# Esp_schm.net
KiCad netlist of a schematic drawn in Altium Designer
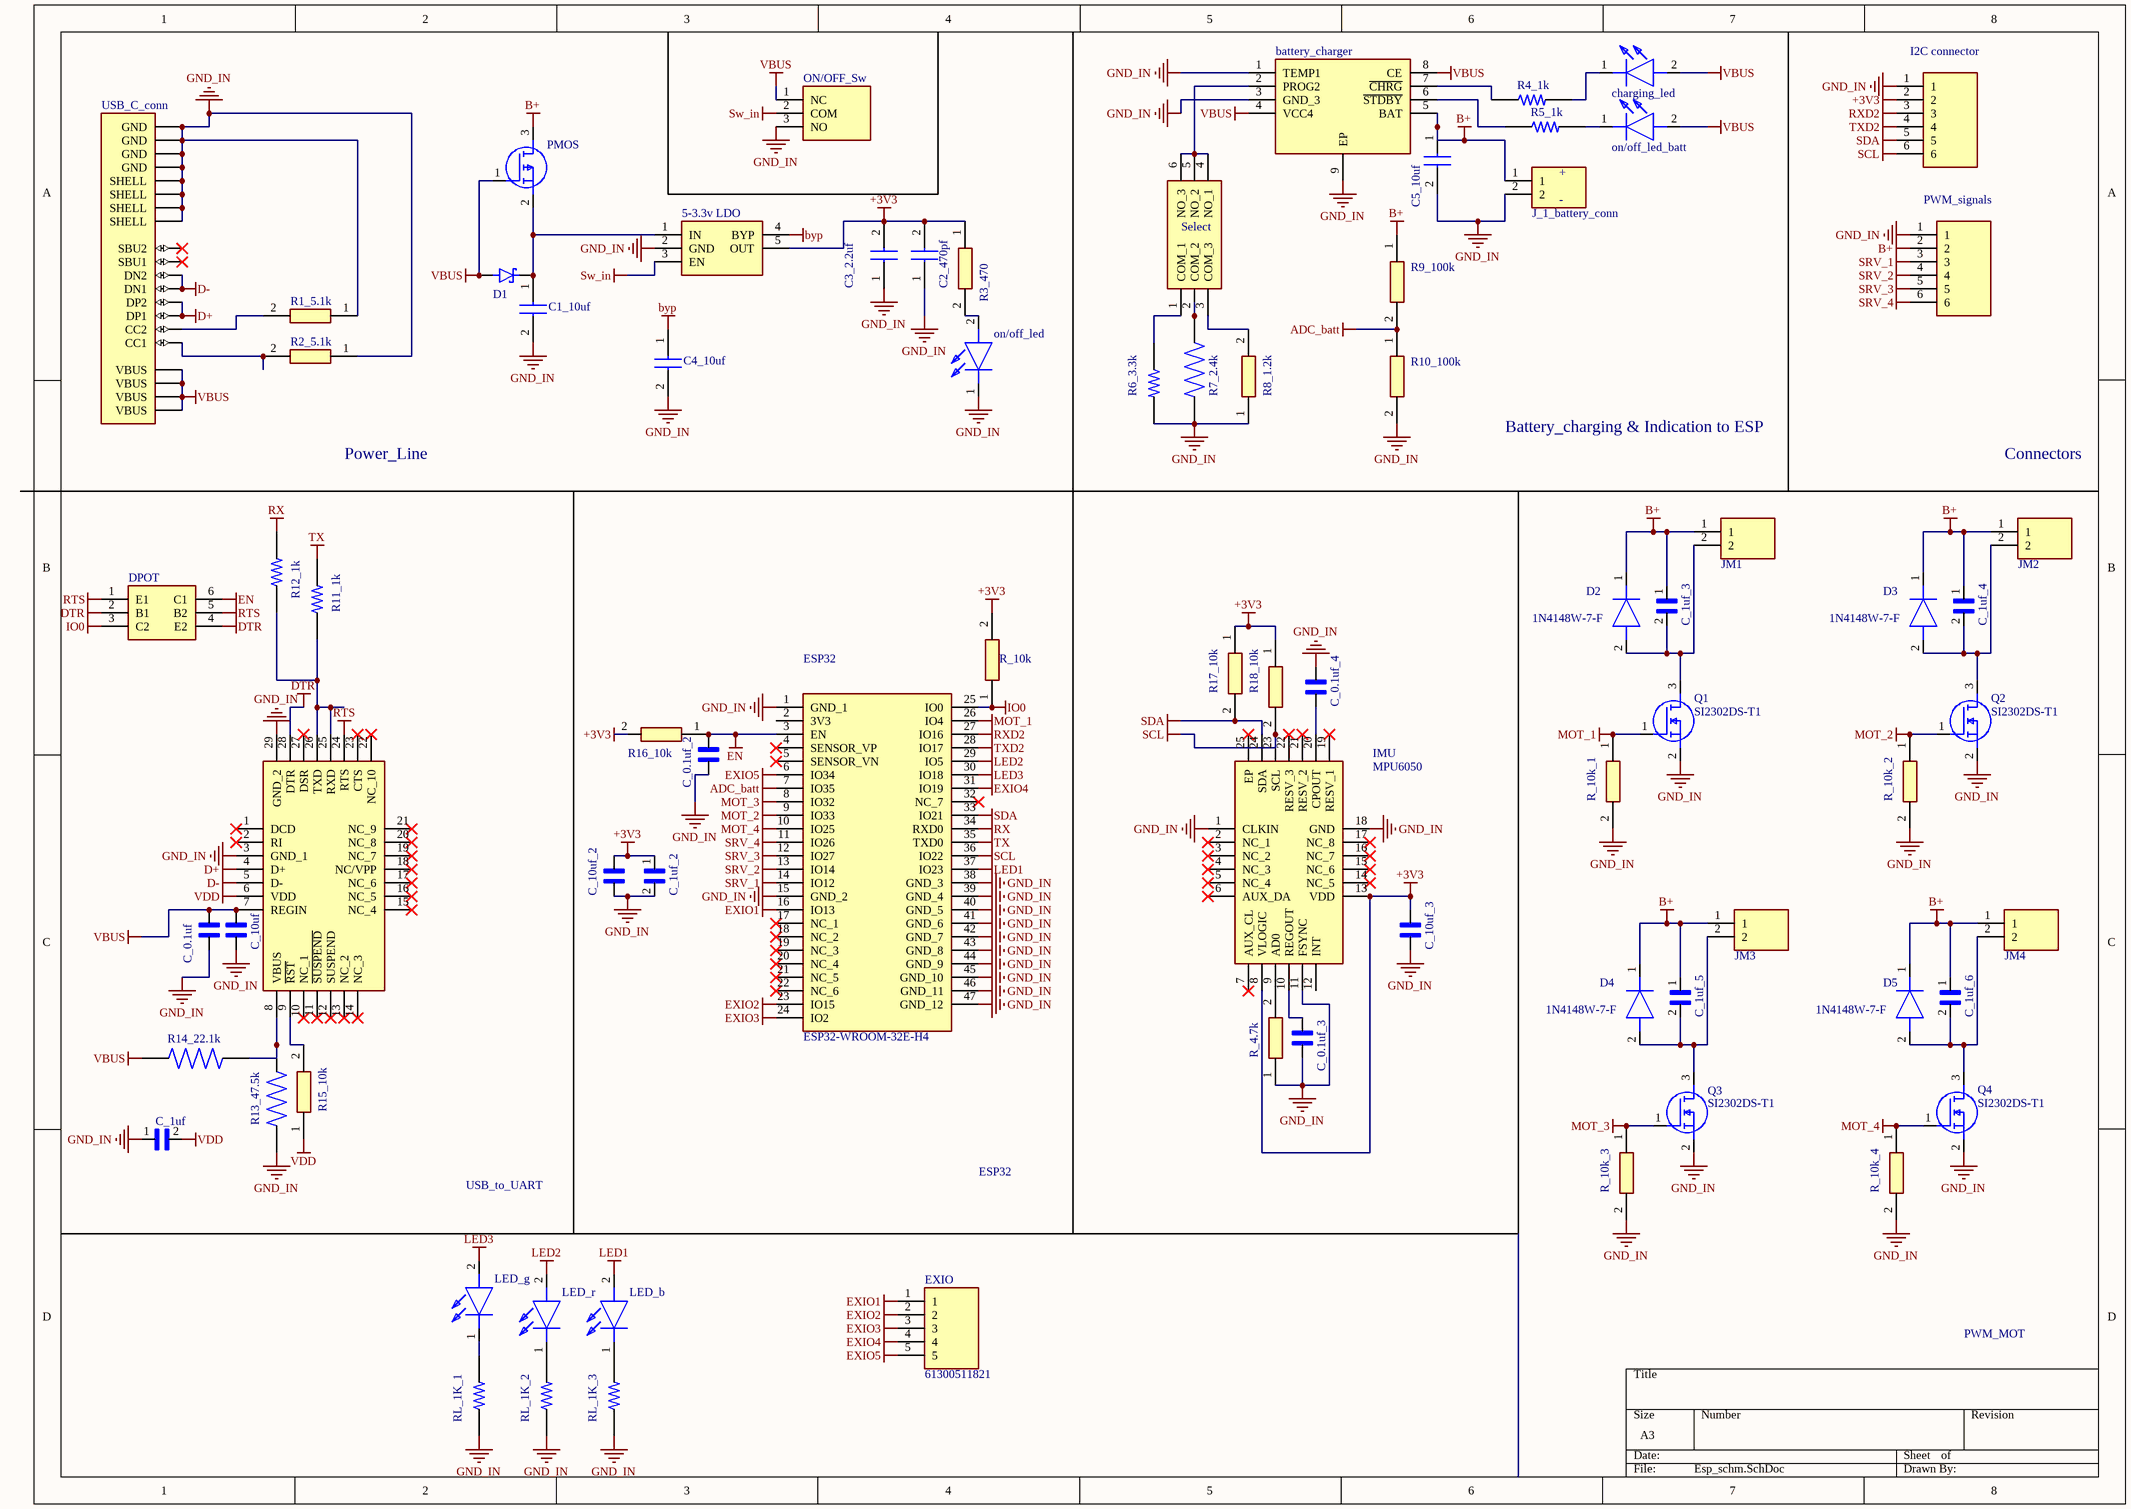
[diagram p0: Esp_schm.SchDoc]

(export (version "E")
  (design (tool "Eeschema 10.0.6"))
  (components
    (comp (ref "5-3.3v LDO")
      (value "MIC5219-3.3YM5-TR")
      (footprint "PcbLib1:SOT95P280X145-5N")
      (description "Integrated Circuit")
      (fields (field (name "MOUSER PART NUMBER") "998-MIC5219-3.3YM5TR"))
      (libsource (lib "*") (part "MIC5219-3.3YM5-TR"))
    )
    (comp (ref "battery_charger")
      (value "TP4056")
      (footprint "PcbLib1:SOIC127P600X175-9N")
      (description "Connector")
      (libsource (lib "*") (part "TP4056"))
    )
    (comp (ref "C1_10uf")
      (value "CGA3EDX7T1A106M080AU")
      (footprint "PcbLib1:CAPC1608X90N")
      (description "Capacitor")
      (fields (field (name "MOUSER PART NUMBER") "810-CGA3EDX7T1A106M0"))
      (libsource (lib "*") (part "CGA3EDX7T1A106M080AU"))
    )
    (comp (ref "C2_470pf")
      (value "02015C471KAT2A")
      (footprint "PcbLib1:CAPC0603X33N")
      (description "Capacitor")
      (fields (field (name "MOUSER PART NUMBER") "581-02015C471KAT2A"))
      (libsource (lib "*") (part "02015C471KAT2A"))
    )
    (comp (ref "C3_2.2uf")
      (value "CL03A225MO5C65C")
      (footprint "PcbLib1:CAPC0603X35N")
      (description "Capacitor")
      (fields (field (name "MOUSER PART NUMBER") "187-CL03A225MO5C65C"))
      (libsource (lib "*") (part "CL03A225MO5C65C"))
    )
    (comp (ref "C4_10uf")
      (value "CGA3EDX7T1A106M080AU")
      (footprint "PcbLib1:CAPC1608X90N")
      (description "Capacitor")
      (fields (field (name "MOUSER PART NUMBER") "810-CGA3EDX7T1A106M0"))
      (libsource (lib "*") (part "CGA3EDX7T1A106M080AU"))
    )
    (comp (ref "C5_10uf")
      (value "CGA3EDX7T1A106M080AU")
      (footprint "PcbLib1:CAPC1608X90N")
      (description "Capacitor")
      (fields (field (name "MOUSER PART NUMBER") "810-CGA3EDX7T1A106M0"))
      (libsource (lib "*") (part "CGA3EDX7T1A106M080AU"))
    )
    (comp (ref "charging_led")
      (value "SML-D12U1WT86")
      (footprint "PcbLib1:LEDC1608X65N")
      (description "LED")
      (fields (field (name "MOUSER PART NUMBER") "755-SML-D12U1WT86"))
      (libsource (lib "*") (part "SML-D12U1WT86"))
    )
    (comp (ref "C_0.1uf")
      (value "GCM188R71C104KA37J")
      (footprint "CAPC1608X90N")
      (description "SMD Capacitor X7R(EIA) with Capacitance: 0.10uF Tol. 10%. Rated Voltage: 16Vdc")
      (fields (field (name "MF") "Murata"))
      (libsource (lib "GCM188R71C104KA37J") (part "GCM188R71C104KA37J"))
    )
    (comp (ref "C_0.1uf_2")
      (value "GCM188R71C104KA37J")
      (footprint "CAPC1608X90N")
      (description "SMD Capacitor X7R(EIA) with Capacitance: 0.10uF Tol. 10%. Rated Voltage: 16Vdc")
      (fields (field (name "MF") "Murata"))
      (libsource (lib "GCM188R71C104KA37J") (part "GCM188R71C104KA37J"))
    )
    (comp (ref "C_0.1uf_3")
      (value "GCM188R71C104KA37J")
      (footprint "CAPC1608X90N")
      (description "SMD Capacitor X7R(EIA) with Capacitance: 0.10uF Tol. 10%. Rated Voltage: 16Vdc")
      (fields (field (name "MF") "Murata"))
      (libsource (lib "GCM188R71C104KA37J") (part "GCM188R71C104KA37J"))
    )
    (comp (ref "C_0.1uf_4")
      (value "GCM188R71C104KA37J")
      (footprint "CAPC1608X90N")
      (description "SMD Capacitor X7R(EIA) with Capacitance: 0.10uF Tol. 10%. Rated Voltage: 16Vdc")
      (fields (field (name "MF") "Murata"))
      (libsource (lib "GCM188R71C104KA37J") (part "GCM188R71C104KA37J"))
    )
    (comp (ref "C_1uf")
      (value "C1608X7R1C105K080AC")
      (footprint "CAPC1608X90N:CAPC1608X90N")
      (description "1ÂµF Â±10% 16V Ceramic Capacitor X7R 0603 (1608 Metric)")
      (fields (field (name "MF") "TDK"))
      (libsource (lib "Schlib1") (part "C1608X7R1C105K080AC"))
    )
    (comp (ref "C_1uf_2")
      (value "C1608X7R1C105K080AC")
      (footprint "CAPC1608X90N:CAPC1608X90N")
      (description "1ÂµF Â±10% 16V Ceramic Capacitor X7R 0603 (1608 Metric)")
      (fields (field (name "MF") "TDK"))
      (libsource (lib "") (part "C1608X7R1C105K080AC_1"))
    )
    (comp (ref "C_1uf_3")
      (value "C1608X7R1C105K080AC")
      (footprint "CAPC1608X90N:CAPC1608X90N")
      (description "1ÂµF Â±10% 16V Ceramic Capacitor X7R 0603 (1608 Metric)")
      (fields (field (name "MF") "TDK"))
      (libsource (lib "") (part "C1608X7R1C105K080AC_1"))
    )
    (comp (ref "C_1uf_4")
      (value "C1608X7R1C105K080AC")
      (footprint "CAPC1608X90N:CAPC1608X90N")
      (description "1ÂµF Â±10% 16V Ceramic Capacitor X7R 0603 (1608 Metric)")
      (fields (field (name "MF") "TDK"))
      (libsource (lib "") (part "C1608X7R1C105K080AC_1"))
    )
    (comp (ref "C_1uf_5")
      (value "C1608X7R1C105K080AC")
      (footprint "CAPC1608X90N:CAPC1608X90N")
      (description "1ÂµF Â±10% 16V Ceramic Capacitor X7R 0603 (1608 Metric)")
      (fields (field (name "MF") "TDK"))
      (libsource (lib "") (part "C1608X7R1C105K080AC_1"))
    )
    (comp (ref "C_1uf_6")
      (value "C1608X7R1C105K080AC")
      (footprint "CAPC1608X90N:CAPC1608X90N")
      (description "1ÂµF Â±10% 16V Ceramic Capacitor X7R 0603 (1608 Metric)")
      (fields (field (name "MF") "TDK"))
      (libsource (lib "") (part "C1608X7R1C105K080AC_1"))
    )
    (comp (ref "C_10uf")
      (value "GRT188R61C106KE13J_1")
      (footprint "CAPC1608X95N")
      (description "SMD capacitor X5R(EIA) with capacitance 10uF Tol.10%. Rated voltage 16Vdc 85C")
      (fields (field (name "MF") "Murata") (field (name "MP") "GRT188R61C106KE13J"))
      (libsource (lib "Schlib1") (part "GRT188R61C106KE13J_1"))
    )
    (comp (ref "C_10uf_2")
      (value "GRT188R61C106KE13J_1")
      (footprint "CAPC1608X95N")
      (description "SMD capacitor X5R(EIA) with capacitance 10uF Tol.10%. Rated voltage 16Vdc 85C")
      (fields (field (name "MF") "Murata") (field (name "MP") "GRT188R61C106KE13J"))
      (libsource (lib "Schlib1") (part "GRT188R61C106KE13J_1"))
    )
    (comp (ref "C_10uf_3")
      (value "GRT188R61C106KE13J_1")
      (footprint "CAPC1608X95N")
      (description "SMD capacitor X5R(EIA) with capacitance 10uF Tol.10%. Rated voltage 16Vdc 85C")
      (fields (field (name "MF") "Murata") (field (name "MP") "GRT188R61C106KE13J"))
      (libsource (lib "Schlib1") (part "GRT188R61C106KE13J_1"))
    )
    (comp (ref "D1")
      (value "SS34")
      (footprint "DIOM7959X265N")
      (description "Diode Schottky 40 V 3A Surface Mount SMC (DO-214AB)")
      (fields (field (name "MF") "onsemi"))
      (libsource (lib "Schlib1") (part "SS34"))
    )
    (comp (ref "D2")
      (value "1N4148W-7-F")
      (footprint "PcbLib1:1N4148W7F")
      (description "Diode")
      (libsource (lib "*") (part "1N4148W-7-F"))
    )
    (comp (ref "D3")
      (value "1N4148W-7-F")
      (footprint "PcbLib1:1N4148W7F")
      (description "Diode")
      (libsource (lib "*") (part "1N4148W-7-F"))
    )
    (comp (ref "D4")
      (value "1N4148W-7-F")
      (footprint "PcbLib1:1N4148W7F")
      (description "Diode")
      (libsource (lib "*") (part "1N4148W-7-F"))
    )
    (comp (ref "D5")
      (value "1N4148W-7-F")
      (footprint "PcbLib1:1N4148W7F")
      (description "Diode")
      (libsource (lib "*") (part "1N4148W-7-F"))
    )
    (comp (ref "DPOT")
      (value "DDC114TU-7-F")
      (footprint "PcbLib1:SOT65P210X110-6N")
      (description "Transistor BJT NPN")
      (fields (field (name "MOUSER PART NUMBER") "621-DDC114TU-F"))
      (libsource (lib "*") (part "DDC114TU-7-F"))
    )
    (comp (ref "ESP32")
      (value "ESP32-WROOM-32E-H4")
      (footprint "PcbLib1:ESP32WROOM32EH4")
      (description "Integrated Circuit")
      (fields (field (name "MOUSER PART NUMBER") "356-ESP32WRM320EH3PS"))
      (libsource (lib "*") (part "ESP32-WROOM-32E-H4"))
    )
    (comp (ref "EXIO")
      (value "61300511821")
      (footprint "PcbLib1:61300511821")
      (description "Connector")
      (fields (field (name "MOUSER PART NUMBER") "710-61300511821"))
      (libsource (lib "*") (part "61300511821"))
    )
    (comp (ref "I2C connector")
      (value "B6B-XH-A_LF__SN_")
      (footprint "PcbLib1:SHDR6W64P0X250_1X6_1740X575X700P")
      (description "Connector")
      (fields
        (field (name "MANUFACTURER_PART_NUMBER") "B6B-XH-A(LF)(SN)")
        (field (name "MOUSER PART NUMBER") "306-B6BXHALFSN")
      )
      (libsource (lib "*") (part "B6B-XH-A_LF__SN_"))
    )
    (comp (ref "IMU")
      (value "MPU6050")
      (footprint "PcbLib1:MPU6050")
      (description "Integrated Circuit")
      (libsource (lib "*") (part "MPU6050"))
    )
    (comp (ref "JM1")
      (value "B2B-XH-A_LF__SN_")
      (footprint "PcbLib1:SHDR2W64P0X250_1X2_740X575X700P")
      (description "Connector")
      (fields
        (field (name "MANUFACTURER_PART_NUMBER") "B2B-XH-A(LF)(SN)")
        (field (name "MOUSER PART NUMBER") "306-B2BXHALFSNP")
      )
      (libsource (lib "*") (part "B2B-XH-A_LF__SN_"))
    )
    (comp (ref "JM2")
      (value "B2B-XH-A_LF__SN_")
      (footprint "PcbLib1:SHDR2W64P0X250_1X2_740X575X700P")
      (description "Connector")
      (fields
        (field (name "MANUFACTURER_PART_NUMBER") "B2B-XH-A(LF)(SN)")
        (field (name "MOUSER PART NUMBER") "306-B2BXHALFSNP")
      )
      (libsource (lib "*") (part "B2B-XH-A_LF__SN_"))
    )
    (comp (ref "JM3")
      (value "B2B-XH-A_LF__SN_")
      (footprint "PcbLib1:SHDR2W64P0X250_1X2_740X575X700P")
      (description "Connector")
      (fields
        (field (name "MANUFACTURER_PART_NUMBER") "B2B-XH-A(LF)(SN)")
        (field (name "MOUSER PART NUMBER") "306-B2BXHALFSNP")
      )
      (libsource (lib "*") (part "B2B-XH-A_LF__SN_"))
    )
    (comp (ref "JM4")
      (value "B2B-XH-A_LF__SN_")
      (footprint "PcbLib1:SHDR2W64P0X250_1X2_740X575X700P")
      (description "Connector")
      (fields
        (field (name "MANUFACTURER_PART_NUMBER") "B2B-XH-A(LF)(SN)")
        (field (name "MOUSER PART NUMBER") "306-B2BXHALFSNP")
      )
      (libsource (lib "*") (part "B2B-XH-A_LF__SN_"))
    )
    (comp (ref "J_1_battery_conn")
      (value "B2B-XH-A_LF__SN_")
      (footprint "PcbLib1:SHDR2W64P0X250_1X2_740X575X700P")
      (description "Connector")
      (fields
        (field (name "MANUFACTURER_PART_NUMBER") "B2B-XH-A(LF)(SN)")
        (field (name "MOUSER PART NUMBER") "306-B2BXHALFSNP")
      )
      (libsource (lib "*") (part "B2B-XH-A_LF__SN_"))
    )
    (comp (ref "LED_b")
      (value "150060BS55040")
      (footprint "PcbLib1:LEDC1608X50N")
      (description "LED")
      (fields (field (name "MOUSER PART NUMBER") "710-150060BS55040"))
      (libsource (lib "*") (part "150060BS55040"))
    )
    (comp (ref "LED_g")
      (value "ASMT-RF45-AN002")
      (footprint "PcbLib1:LEDC1608X55N")
      (description "LED")
      (fields (field (name "MOUSER PART NUMBER") "630-ASMT-RF45-AN002"))
      (libsource (lib "*") (part "ASMT-RF45-AN002"))
    )
    (comp (ref "LED_r")
      (value "KR_DELPS1.22-VGVI-23-H3Q4")
      (footprint "PcbLib1:KRDELPS122VGVI23H3Q4")
      (description "LED")
      (fields
        (field (name "MANUFACTURER_PART_NUMBER") "KR DELPS1.22-VGVI-23-H3Q4")
        (field (name "MOUSER PART NUMBER") "720-KRDELPS122VGVI3H")
      )
      (libsource (lib "*") (part "KR_DELPS1.22-VGVI-23-H3Q4"))
    )
    (comp (ref "on/off_led")
      (value "LB_Q39G-L2OO-35-1")
      (footprint "PcbLib1:LEDC1608X40N")
      (description "LED")
      (fields
        (field (name "MANUFACTURER_PART_NUMBER") "LB Q39G-L2OO-35-1")
        (field (name "MOUSER PART NUMBER") "720-LBQ39GL2N2351")
      )
      (libsource (lib "*") (part "LB_Q39G-L2OO-35-1"))
    )
    (comp (ref "on/off_led_batt")
      (value "LB_Q39G-L2OO-35-1")
      (footprint "PcbLib1:LEDC1608X40N")
      (description "LED")
      (fields
        (field (name "MANUFACTURER_PART_NUMBER") "LB Q39G-L2OO-35-1")
        (field (name "MOUSER PART NUMBER") "720-LBQ39GL2N2351")
      )
      (libsource (lib "*") (part "LB_Q39G-L2OO-35-1"))
    )
    (comp (ref "ON/OFF_Sw")
      (value "SLW-883935-2A-D")
      (footprint "PcbLib1:SLW8839352AD")
      (description "Switch")
      (fields (field (name "MOUSER PART NUMBER") "179-SLW-883935-2A-D"))
      (libsource (lib "*") (part "SLW-883935-2A-D"))
    )
    (comp (ref "PMOS")
      (value "AO3401A")
      (footprint "SamacSys:SOT95P280X125-3N")
      (description "MOSFET (P-Channel)")
      (libsource (lib "*") (part "AO3401A"))
    )
    (comp (ref "PWM_signals")
      (value "B6B-XH-A_LF__SN_")
      (footprint "PcbLib1:SHDR6W64P0X250_1X6_1740X575X700P")
      (description "Connector")
      (fields
        (field (name "MANUFACTURER_PART_NUMBER") "B6B-XH-A(LF)(SN)")
        (field (name "MOUSER PART NUMBER") "306-B6BXHALFSN")
      )
      (libsource (lib "*") (part "B6B-XH-A_LF__SN_"))
    )
    (comp (ref "Q1")
      (value "SI2302DS-T1")
      (footprint "PcbLib1:SOT95P237X112-3N")
      (description "MOSFET (N-Channel)")
      (fields (field (name "MOUSER PART NUMBER") "781-SI2302DS"))
      (libsource (lib "*") (part "SI2302DS-T1"))
    )
    (comp (ref "Q2")
      (value "SI2302DS-T1")
      (footprint "PcbLib1:SOT95P237X112-3N")
      (description "MOSFET (N-Channel)")
      (fields (field (name "MOUSER PART NUMBER") "781-SI2302DS"))
      (libsource (lib "*") (part "SI2302DS-T1"))
    )
    (comp (ref "Q3")
      (value "SI2302DS-T1")
      (footprint "PcbLib1:SOT95P237X112-3N")
      (description "MOSFET (N-Channel)")
      (fields (field (name "MOUSER PART NUMBER") "781-SI2302DS"))
      (libsource (lib "*") (part "SI2302DS-T1"))
    )
    (comp (ref "Q4")
      (value "SI2302DS-T1")
      (footprint "PcbLib1:SOT95P237X112-3N")
      (description "MOSFET (N-Channel)")
      (fields (field (name "MOUSER PART NUMBER") "781-SI2302DS"))
      (libsource (lib "*") (part "SI2302DS-T1"))
    )
    (comp (ref "R1_5.1k")
      (value "ERA-3VEB5101V")
      (footprint "SamacSys:ERA3KV_(0603)")
      (description "Resistor")
      (fields (field (name "MOUSER PART NUMBER") "667-ERA-3VEB5101V"))
      (libsource (lib "Schlib1") (part "ERA-3VEB5101V"))
    )
    (comp (ref "R2_5.1k")
      (value "ERA-3VEB5101V")
      (footprint "SamacSys:ERA3KV_(0603)")
      (description "Resistor")
      (fields (field (name "MOUSER PART NUMBER") "667-ERA-3VEB5101V"))
      (libsource (lib "Schlib1") (part "ERA-3VEB5101V"))
    )
    (comp (ref "R3_470")
      (value "ERJ-1GJF4700C")
      (footprint "PcbLib1:ERJ1GJJ2R4C")
      (description "Resistor")
      (fields (field (name "MOUSER PART NUMBER") "667-ERJ-1GJF4700C"))
      (libsource (lib "*") (part "ERJ-1GJF4700C"))
    )
    (comp (ref "R4_1k")
      (value "RC0603FR-071KL")
      (footprint "RESC1607X60N")
      (description "1 kOhms Â±1% 0.1W, 1/10W Chip Resistor 0603 (1608 Metric) Moisture Resistant Thick Film")
      (fields (field (name "MF") "Yageo"))
      (libsource (lib "Schlib1") (part "RC0603FR-071KL"))
    )
    (comp (ref "R5_1k")
      (value "RC0603FR-071KL")
      (footprint "RESC1607X60N")
      (description "1 kOhms Â±1% 0.1W, 1/10W Chip Resistor 0603 (1608 Metric) Moisture Resistant Thick Film")
      (fields (field (name "MF") "Yageo"))
      (libsource (lib "Schlib1") (part "RC0603FR-071KL"))
    )
    (comp (ref "R6_3.3k")
      (value "RC0603FR-073K3L")
      (footprint "RESC1607X60N")
      (description "3.3 kOhms ±1% 0.1W, 1/10W Chip Resistor 0603 (1608 Metric) Moisture Resistant Thick Film")
      (fields (field (name "MF") "Yageo"))
      (libsource (lib "Schlib1") (part "RC0603FR-073K3L"))
    )
    (comp (ref "R7_2.4k")
      (value "RC0603FR-072K4L")
      (footprint "RESC1607X60N")
      (description "2.4 kOhms Â±1% 0.1W, 1/10W Chip Resistor 0603 (1608 Metric) Moisture Resistant Thick Film")
      (fields (field (name "MF") "Yageo"))
      (libsource (lib "Schlib1") (part "RC0603FR-072K4L"))
    )
    (comp (ref "R8_1.2k")
      (value "ERJ-3GEYJ122V")
      (footprint "PcbLib1:ERJ3EKF1000V")
      (description "Resistor")
      (fields (field (name "MOUSER PART NUMBER") "667-ERJ-3GEYJ122V"))
      (libsource (lib "*") (part "ERJ-3GEYJ122V"))
    )
    (comp (ref "R9_100k")
      (value "RC0805FR-7W100KL")
      (footprint "PcbLib1:RESC2012X60N")
      (description "Resistor")
      (fields (field (name "MOUSER PART NUMBER") "603-RC0805FR-7W100KL"))
      (libsource (lib "*") (part "RC0805FR-7W100KL"))
    )
    (comp (ref "R10_100k")
      (value "RC0805FR-7W100KL")
      (footprint "PcbLib1:RESC2012X60N")
      (description "Resistor")
      (fields (field (name "MOUSER PART NUMBER") "603-RC0805FR-7W100KL"))
      (libsource (lib "*") (part "RC0805FR-7W100KL"))
    )
    (comp (ref "R11_1k")
      (value "RC0603FR-071KL")
      (footprint "RESC1607X60N")
      (description "1 kOhms Â±1% 0.1W, 1/10W Chip Resistor 0603 (1608 Metric) Moisture Resistant Thick Film")
      (fields (field (name "MF") "Yageo"))
      (libsource (lib "Schlib1") (part "RC0603FR-071KL"))
    )
    (comp (ref "R12_1k")
      (value "RC0603FR-071KL")
      (footprint "RESC1607X60N")
      (description "1 kOhms Â±1% 0.1W, 1/10W Chip Resistor 0603 (1608 Metric) Moisture Resistant Thick Film")
      (fields (field (name "MF") "Yageo"))
      (libsource (lib "Schlib1") (part "RC0603FR-071KL"))
    )
    (comp (ref "R13_47.5k")
      (value "CRCW060347K5FKEA")
      (footprint "RESC1508X50N")
      (fields (field (name "MF") "Vishay"))
      (libsource (lib "Schlib1") (part "CRCW060347K5FKEA"))
    )
    (comp (ref "R14_22.1k")
      (value "CRCW060322K1FKEA")
      (footprint "RESC1508X50N")
      (fields (field (name "MF") "Vishay Dale"))
      (libsource (lib "CRCW060322K1FKEA") (part "CRCW060322K1FKEA"))
    )
    (comp (ref "R15_10k")
      (value "CRCW060310K0FKEA")
      (footprint "PcbLib1:RESC1608X50N")
      (description "Resistor")
      (fields (field (name "MOUSER PART NUMBER") "71-CRCW0603-10K-E3"))
      (libsource (lib "") (part "CRCW060310K0FKEA_2"))
    )
    (comp (ref "R16_10k")
      (value "CRCW060310K0FKEA")
      (footprint "PcbLib1:RESC1608X50N")
      (description "Resistor")
      (fields (field (name "MOUSER PART NUMBER") "71-CRCW0603-10K-E3"))
      (libsource (lib "*") (part "CRCW060310K0FKEA"))
    )
    (comp (ref "R17_10k")
      (value "CRCW060310K0FKEA")
      (footprint "PcbLib1:RESC1608X50N")
      (description "Resistor")
      (fields (field (name "MOUSER PART NUMBER") "71-CRCW0603-10K-E3"))
      (libsource (lib "") (part "CRCW060310K0FKEA_1"))
    )
    (comp (ref "R18_10k")
      (value "CRCW060310K0FKEA")
      (footprint "PcbLib1:RESC1608X50N")
      (description "Resistor")
      (fields (field (name "MOUSER PART NUMBER") "71-CRCW0603-10K-E3"))
      (libsource (lib "") (part "CRCW060310K0FKEA_1"))
    )
    (comp (ref "RL_1K_1")
      (value "RC0603FR-071KL")
      (footprint "RESC1607X60N")
      (description "1 kOhms Â±1% 0.1W, 1/10W Chip Resistor 0603 (1608 Metric) Moisture Resistant Thick Film")
      (fields (field (name "MF") "Yageo"))
      (libsource (lib "Schlib1") (part "RC0603FR-071KL"))
    )
    (comp (ref "RL_1K_2")
      (value "RC0603FR-071KL")
      (footprint "RESC1607X60N")
      (description "1 kOhms Â±1% 0.1W, 1/10W Chip Resistor 0603 (1608 Metric) Moisture Resistant Thick Film")
      (fields (field (name "MF") "Yageo"))
      (libsource (lib "Schlib1") (part "RC0603FR-071KL"))
    )
    (comp (ref "RL_1K_3")
      (value "RC0603FR-071KL")
      (footprint "RESC1607X60N")
      (description "1 kOhms Â±1% 0.1W, 1/10W Chip Resistor 0603 (1608 Metric) Moisture Resistant Thick Film")
      (fields (field (name "MF") "Yageo"))
      (libsource (lib "Schlib1") (part "RC0603FR-071KL"))
    )
    (comp (ref "R_4.7k")
      (value "GWCR0603-4K7FT5")
      (footprint "PcbLib1:RESC1608X55N")
      (description "Resistor")
      (fields (field (name "MOUSER PART NUMBER") "756-GWCR0603-4K7FT5"))
      (libsource (lib "*") (part "GWCR0603-4K7FT5"))
    )
    (comp (ref "R_10k")
      (value "CRCW060310K0FKEA")
      (footprint "PcbLib1:RESC1608X50N")
      (description "Resistor")
      (fields (field (name "MOUSER PART NUMBER") "71-CRCW0603-10K-E3"))
      (libsource (lib "") (part "CRCW060310K0FKEA_2"))
    )
    (comp (ref "R_10k_1")
      (value "CRCW060310K0FKEA")
      (footprint "PcbLib1:RESC1608X50N")
      (description "Resistor")
      (fields (field (name "MOUSER PART NUMBER") "71-CRCW0603-10K-E3"))
      (libsource (lib "") (part "CRCW060310K0FKEA_1"))
    )
    (comp (ref "R_10k_2")
      (value "CRCW060310K0FKEA")
      (footprint "PcbLib1:RESC1608X50N")
      (description "Resistor")
      (fields (field (name "MOUSER PART NUMBER") "71-CRCW0603-10K-E3"))
      (libsource (lib "") (part "CRCW060310K0FKEA_1"))
    )
    (comp (ref "R_10k_3")
      (value "CRCW060310K0FKEA")
      (footprint "PcbLib1:RESC1608X50N")
      (description "Resistor")
      (fields (field (name "MOUSER PART NUMBER") "71-CRCW0603-10K-E3"))
      (libsource (lib "") (part "CRCW060310K0FKEA_1"))
    )
    (comp (ref "R_10k_4")
      (value "CRCW060310K0FKEA")
      (footprint "PcbLib1:RESC1608X50N")
      (description "Resistor")
      (fields (field (name "MOUSER PART NUMBER") "71-CRCW0603-10K-E3"))
      (libsource (lib "") (part "CRCW060310K0FKEA_1"))
    )
    (comp (ref "Select")
      (value "DS01-254-S-03BE")
      (footprint "PcbLib1:DS01254S03BE")
      (description "Switch")
      (fields (field (name "MOUSER PART NUMBER") "490-DS01-254-S-03BE"))
      (libsource (lib "*") (part "DS01-254-S-03BE"))
    )
    (comp (ref "USB_C_conn")
      (value "USB4085-GF-A_REVB")
      (footprint "GCT_USB4085-GF-A_REVB")
      (fields (field (name "MF") "Global Connector Technology") (field (name "MP") "USB4085-GF-A"))
      (libsource (lib "Schlib1") (part "USB4085-GF-A_REVB"))
    )
    (comp (ref "USB_to_UART")
      (value "CP2102-GM")
      (footprint "PcbLib1:QFN50P500X500X100-29N-D")
      (description "Integrated Circuit")
      (fields (field (name "MOUSER PART NUMBER") "634-CP2102-GM"))
      (libsource (lib "*") (part "CP2102-GM"))
    )
  )
  (nets
    (net (code "1") (name "+3V3") (class "Default")
      (node (ref "5-3.3v LDO") (pin "5") (pinfunction "OUT_5") (pintype "passive"))
      (node (ref "C2_470pf") (pin "2") (pinfunction "2_2") (pintype "passive"))
      (node (ref "C3_2.2uf") (pin "2") (pinfunction "2_2") (pintype "passive"))
      (node (ref "C_10uf_2") (pin "2") (pinfunction "2_2") (pintype "passive"))
      (node (ref "C_10uf_3") (pin "2") (pinfunction "2_2") (pintype "passive"))
      (node (ref "C_1uf_2") (pin "1") (pinfunction "1_1") (pintype "passive"))
      (node (ref "I2C connector") (pin "2") (pinfunction "2_2") (pintype "passive"))
      (node (ref "IMU") (pin "13") (pinfunction "VDD_13") (pintype "passive"))
      (node (ref "IMU") (pin "8") (pinfunction "VLOGIC_8") (pintype "passive"))
      (node (ref "R16_10k") (pin "2") (pinfunction "2_2") (pintype "passive"))
      (node (ref "R17_10k") (pin "1") (pinfunction "1_1") (pintype "passive"))
      (node (ref "R18_10k") (pin "1") (pinfunction "1_1") (pintype "passive"))
      (node (ref "R3_470") (pin "1") (pinfunction "1_1") (pintype "passive"))
      (node (ref "R_10k") (pin "2") (pinfunction "2_2") (pintype "passive"))
    )
    (net (code "2") (name "ADC_batt") (class "Default")
      (node (ref "ESP32") (pin "7") (pinfunction "IO35_7") (pintype "passive"))
      (node (ref "R10_100k") (pin "1") (pinfunction "1_1") (pintype "passive"))
      (node (ref "R9_100k") (pin "2") (pinfunction "2_2") (pintype "passive"))
    )
    (net (code "3") (name "B+") (class "Default")
      (node (ref "C5_10uf") (pin "1") (pinfunction "1_1") (pintype "passive"))
      (node (ref "C_1uf_3") (pin "1") (pinfunction "1_1") (pintype "passive"))
      (node (ref "C_1uf_4") (pin "1") (pinfunction "1_1") (pintype "passive"))
      (node (ref "C_1uf_5") (pin "1") (pinfunction "1_1") (pintype "passive"))
      (node (ref "C_1uf_6") (pin "1") (pinfunction "1_1") (pintype "passive"))
      (node (ref "D2") (pin "1") (pinfunction "K_1") (pintype "passive"))
      (node (ref "D3") (pin "1") (pinfunction "K_1") (pintype "passive"))
      (node (ref "D4") (pin "1") (pinfunction "K_1") (pintype "passive"))
      (node (ref "D5") (pin "1") (pinfunction "K_1") (pintype "passive"))
      (node (ref "JM1") (pin "1") (pinfunction "1_1") (pintype "passive"))
      (node (ref "JM2") (pin "1") (pinfunction "1_1") (pintype "passive"))
      (node (ref "JM3") (pin "1") (pinfunction "1_1") (pintype "passive"))
      (node (ref "JM4") (pin "1") (pinfunction "1_1") (pintype "passive"))
      (node (ref "J_1_battery_conn") (pin "1") (pinfunction "1_1") (pintype "passive"))
      (node (ref "PMOS") (pin "3") (pinfunction "D_3") (pintype "passive"))
      (node (ref "PWM_signals") (pin "2") (pinfunction "2_2") (pintype "passive"))
      (node (ref "R9_100k") (pin "1") (pinfunction "1_1") (pintype "passive"))
      (node (ref "battery_charger") (pin "5") (pinfunction "BAT_5") (pintype "passive"))
    )
    (net (code "4") (name "D+") (class "Default")
      (node (ref "USB_C_conn") (pin "A6") (pinfunction "DP1_A6") (pintype "bidirectional"))
      (node (ref "USB_C_conn") (pin "B6") (pinfunction "DP2_B6") (pintype "bidirectional"))
      (node (ref "USB_to_UART") (pin "4") (pinfunction "D+_4") (pintype "passive"))
    )
    (net (code "5") (name "D-") (class "Default")
      (node (ref "USB_C_conn") (pin "A7") (pinfunction "DN1_A7") (pintype "bidirectional"))
      (node (ref "USB_C_conn") (pin "B7") (pinfunction "DN2_B7") (pintype "bidirectional"))
      (node (ref "USB_to_UART") (pin "5") (pinfunction "D-_5") (pintype "passive"))
    )
    (net (code "6") (name "DTR") (class "Default")
      (node (ref "DPOT") (pin "2") (pinfunction "B1_2") (pintype "passive"))
      (node (ref "DPOT") (pin "4") (pinfunction "E2_4") (pintype "passive"))
      (node (ref "USB_to_UART") (pin "28") (pinfunction "DTR_28") (pintype "passive"))
    )
    (net (code "7") (name "EN") (class "Default")
      (node (ref "C_0.1uf_2") (pin "2") (pinfunction "2_2") (pintype "passive"))
      (node (ref "DPOT") (pin "6") (pinfunction "C1_6") (pintype "passive"))
      (node (ref "ESP32") (pin "3") (pinfunction "EN_3") (pintype "passive"))
      (node (ref "R16_10k") (pin "1") (pinfunction "1_1") (pintype "passive"))
    )
    (net (code "8") (name "EXIO1") (class "Default")
      (node (ref "ESP32") (pin "16") (pinfunction "IO13_16") (pintype "passive"))
      (node (ref "EXIO") (pin "1") (pinfunction "1_1") (pintype "passive"))
    )
    (net (code "9") (name "EXIO2") (class "Default")
      (node (ref "ESP32") (pin "23") (pinfunction "IO15_23") (pintype "passive"))
      (node (ref "EXIO") (pin "2") (pinfunction "2_2") (pintype "passive"))
    )
    (net (code "10") (name "EXIO3") (class "Default")
      (node (ref "ESP32") (pin "24") (pinfunction "IO2_24") (pintype "passive"))
      (node (ref "EXIO") (pin "3") (pinfunction "3_3") (pintype "passive"))
    )
    (net (code "11") (name "EXIO4") (class "Default")
      (node (ref "ESP32") (pin "31") (pinfunction "IO19_31") (pintype "passive"))
      (node (ref "EXIO") (pin "4") (pinfunction "4_4") (pintype "passive"))
    )
    (net (code "12") (name "EXIO5") (class "Default")
      (node (ref "ESP32") (pin "6") (pinfunction "IO34_6") (pintype "passive"))
      (node (ref "EXIO") (pin "5") (pinfunction "5_5") (pintype "passive"))
    )
    (net (code "13") (name "GND_IN") (class "Default")
      (node (ref "5-3.3v LDO") (pin "2") (pinfunction "GND_2") (pintype "passive"))
      (node (ref "C1_10uf") (pin "2") (pinfunction "2_2") (pintype "passive"))
      (node (ref "C2_470pf") (pin "1") (pinfunction "1_1") (pintype "passive"))
      (node (ref "C3_2.2uf") (pin "1") (pinfunction "1_1") (pintype "passive"))
      (node (ref "C4_10uf") (pin "2") (pinfunction "2_2") (pintype "passive"))
      (node (ref "C5_10uf") (pin "2") (pinfunction "2_2") (pintype "passive"))
      (node (ref "C_0.1uf") (pin "1") (pinfunction "1_1") (pintype "passive"))
      (node (ref "C_0.1uf_2") (pin "1") (pinfunction "1_1") (pintype "passive"))
      (node (ref "C_0.1uf_3") (pin "1") (pinfunction "1_1") (pintype "passive"))
      (node (ref "C_0.1uf_4") (pin "2") (pinfunction "2_2") (pintype "passive"))
      (node (ref "C_10uf") (pin "1") (pinfunction "1_1") (pintype "passive"))
      (node (ref "C_10uf_2") (pin "1") (pinfunction "1_1") (pintype "passive"))
      (node (ref "C_10uf_3") (pin "1") (pinfunction "1_1") (pintype "passive"))
      (node (ref "C_1uf") (pin "1") (pinfunction "1_1") (pintype "passive"))
      (node (ref "C_1uf_2") (pin "2") (pinfunction "2_2") (pintype "passive"))
      (node (ref "ESP32") (pin "1") (pinfunction "GND_1_1") (pintype "passive"))
      (node (ref "ESP32") (pin "15") (pinfunction "GND_2_15") (pintype "passive"))
      (node (ref "ESP32") (pin "38") (pinfunction "GND_3_38") (pintype "passive"))
      (node (ref "ESP32") (pin "39") (pinfunction "GND_4_39") (pintype "passive"))
      (node (ref "ESP32") (pin "40") (pinfunction "GND_5_40") (pintype "passive"))
      (node (ref "ESP32") (pin "41") (pinfunction "GND_6_41") (pintype "passive"))
      (node (ref "ESP32") (pin "42") (pinfunction "GND_7_42") (pintype "passive"))
      (node (ref "ESP32") (pin "43") (pinfunction "GND_8_43") (pintype "passive"))
      (node (ref "ESP32") (pin "44") (pinfunction "GND_9_44") (pintype "passive"))
      (node (ref "ESP32") (pin "45") (pinfunction "GND_10_45") (pintype "passive"))
      (node (ref "ESP32") (pin "46") (pinfunction "GND_11_46") (pintype "passive"))
      (node (ref "ESP32") (pin "47") (pinfunction "GND_12_47") (pintype "passive"))
      (node (ref "I2C connector") (pin "1") (pinfunction "1_1") (pintype "passive"))
      (node (ref "IMU") (pin "1") (pinfunction "CLKIN_1") (pintype "passive"))
      (node (ref "IMU") (pin "11") (pinfunction "FSYNC_11") (pintype "passive"))
      (node (ref "IMU") (pin "18") (pinfunction "GND_18") (pintype "passive"))
      (node (ref "J_1_battery_conn") (pin "2") (pinfunction "2_2") (pintype "passive"))
      (node (ref "ON/OFF_Sw") (pin "3") (pinfunction "NO_3") (pintype "passive"))
      (node (ref "PWM_signals") (pin "1") (pinfunction "1_1") (pintype "passive"))
      (node (ref "Q1") (pin "2") (pinfunction "S_2") (pintype "passive"))
      (node (ref "Q2") (pin "2") (pinfunction "S_2") (pintype "passive"))
      (node (ref "Q3") (pin "2") (pinfunction "S_2") (pintype "passive"))
      (node (ref "Q4") (pin "2") (pinfunction "S_2") (pintype "passive"))
      (node (ref "R10_100k") (pin "2") (pinfunction "2_2") (pintype "passive"))
      (node (ref "R13_47.5k") (pin "1") (pinfunction "1_1") (pintype "passive"))
      (node (ref "R1_5.1k") (pin "1") (pinfunction "1_1") (pintype "passive"))
      (node (ref "R2_5.1k") (pin "1") (pinfunction "1_1") (pintype "passive"))
      (node (ref "R6_3.3k") (pin "2") (pinfunction "2_2") (pintype "passive"))
      (node (ref "R7_2.4k") (pin "1") (pinfunction "1_1") (pintype "passive"))
      (node (ref "R8_1.2k") (pin "1") (pinfunction "1_1") (pintype "passive"))
      (node (ref "RL_1K_1") (pin "1") (pinfunction "1_1") (pintype "passive"))
      (node (ref "RL_1K_2") (pin "1") (pinfunction "1_1") (pintype "passive"))
      (node (ref "RL_1K_3") (pin "1") (pinfunction "1_1") (pintype "passive"))
      (node (ref "R_10k_1") (pin "2") (pinfunction "2_2") (pintype "passive"))
      (node (ref "R_10k_2") (pin "2") (pinfunction "2_2") (pintype "passive"))
      (node (ref "R_10k_3") (pin "2") (pinfunction "2_2") (pintype "passive"))
      (node (ref "R_10k_4") (pin "2") (pinfunction "2_2") (pintype "passive"))
      (node (ref "R_4.7k") (pin "1") (pinfunction "1_1") (pintype "passive"))
      (node (ref "USB_C_conn") (pin "A1") (pinfunction "GND_A1") (pintype "power_in"))
      (node (ref "USB_C_conn") (pin "A12") (pinfunction "GND_A12") (pintype "power_in"))
      (node (ref "USB_C_conn") (pin "B1") (pinfunction "GND_B1") (pintype "power_in"))
      (node (ref "USB_C_conn") (pin "B12") (pinfunction "GND_B12") (pintype "power_in"))
      (node (ref "USB_C_conn") (pin "S1") (pinfunction "SHELL_S1") (pintype "passive"))
      (node (ref "USB_C_conn") (pin "S2") (pinfunction "SHELL_S2") (pintype "passive"))
      (node (ref "USB_C_conn") (pin "S3") (pinfunction "SHELL_S3") (pintype "passive"))
      (node (ref "USB_C_conn") (pin "S4") (pinfunction "SHELL_S4") (pintype "passive"))
      (node (ref "USB_to_UART") (pin "29") (pinfunction "GND_2_29") (pintype "passive"))
      (node (ref "USB_to_UART") (pin "3") (pinfunction "GND_1_3") (pintype "passive"))
      (node (ref "battery_charger") (pin "1") (pinfunction "TEMP1_1") (pintype "passive"))
      (node (ref "battery_charger") (pin "3") (pinfunction "GND_3_3") (pintype "passive"))
      (node (ref "battery_charger") (pin "9") (pinfunction "EP_9") (pintype "passive"))
      (node (ref "on/off_led") (pin "1") (pinfunction "K_1") (pintype "passive"))
    )
    (net (code "14") (name "IO0") (class "Default")
      (node (ref "DPOT") (pin "3") (pinfunction "C2_3") (pintype "passive"))
      (node (ref "ESP32") (pin "25") (pinfunction "IO0_25") (pintype "passive"))
      (node (ref "R_10k") (pin "1") (pinfunction "1_1") (pintype "passive"))
    )
    (net (code "15") (name "LED1") (class "Default")
      (node (ref "ESP32") (pin "37") (pinfunction "IO23_37") (pintype "passive"))
      (node (ref "LED_b") (pin "2") (pinfunction "A_2") (pintype "passive"))
    )
    (net (code "16") (name "LED2") (class "Default")
      (node (ref "ESP32") (pin "29") (pinfunction "IO5_29") (pintype "passive"))
      (node (ref "LED_r") (pin "2") (pinfunction "A_2") (pintype "passive"))
    )
    (net (code "17") (name "LED3") (class "Default")
      (node (ref "ESP32") (pin "30") (pinfunction "IO18_30") (pintype "passive"))
      (node (ref "LED_g") (pin "2") (pinfunction "A_2") (pintype "passive"))
    )
    (net (code "18") (name "MOT_1") (class "Default")
      (node (ref "ESP32") (pin "26") (pinfunction "IO4_26") (pintype "passive"))
      (node (ref "Q1") (pin "1") (pinfunction "G_1") (pintype "passive"))
      (node (ref "R_10k_1") (pin "1") (pinfunction "1_1") (pintype "passive"))
    )
    (net (code "19") (name "MOT_2") (class "Default")
      (node (ref "ESP32") (pin "9") (pinfunction "IO33_9") (pintype "passive"))
      (node (ref "Q2") (pin "1") (pinfunction "G_1") (pintype "passive"))
      (node (ref "R_10k_2") (pin "1") (pinfunction "1_1") (pintype "passive"))
    )
    (net (code "20") (name "MOT_3") (class "Default")
      (node (ref "ESP32") (pin "8") (pinfunction "IO32_8") (pintype "passive"))
      (node (ref "Q3") (pin "1") (pinfunction "G_1") (pintype "passive"))
      (node (ref "R_10k_3") (pin "1") (pinfunction "1_1") (pintype "passive"))
    )
    (net (code "21") (name "MOT_4") (class "Default")
      (node (ref "ESP32") (pin "10") (pinfunction "IO25_10") (pintype "passive"))
      (node (ref "Q4") (pin "1") (pinfunction "G_1") (pintype "passive"))
      (node (ref "R_10k_4") (pin "1") (pinfunction "1_1") (pintype "passive"))
    )
    (net (code "22") (name "Net-(5-3.3v LDO-IN)") (class "Default")
      (node (ref "5-3.3v LDO") (pin "1") (pinfunction "IN_1") (pintype "passive"))
      (node (ref "C1_10uf") (pin "1") (pinfunction "1_1") (pintype "passive"))
      (node (ref "D1") (pin "C") (pinfunction "K_C") (pintype "passive"))
      (node (ref "PMOS") (pin "2") (pinfunction "S_2") (pintype "passive"))
    )
    (net (code "23") (name "Net-(D2-A)") (class "Default")
      (node (ref "C_1uf_3") (pin "2") (pinfunction "2_2") (pintype "passive"))
      (node (ref "D2") (pin "2") (pinfunction "A_2") (pintype "passive"))
      (node (ref "JM1") (pin "2") (pinfunction "2_2") (pintype "passive"))
      (node (ref "Q1") (pin "3") (pinfunction "D_3") (pintype "passive"))
    )
    (net (code "24") (name "Net-(D3-A)") (class "Default")
      (node (ref "C_1uf_4") (pin "2") (pinfunction "2_2") (pintype "passive"))
      (node (ref "D3") (pin "2") (pinfunction "A_2") (pintype "passive"))
      (node (ref "JM2") (pin "2") (pinfunction "2_2") (pintype "passive"))
      (node (ref "Q2") (pin "3") (pinfunction "D_3") (pintype "passive"))
    )
    (net (code "25") (name "Net-(D4-A)") (class "Default")
      (node (ref "C_1uf_5") (pin "2") (pinfunction "2_2") (pintype "passive"))
      (node (ref "D4") (pin "2") (pinfunction "A_2") (pintype "passive"))
      (node (ref "JM3") (pin "2") (pinfunction "2_2") (pintype "passive"))
      (node (ref "Q3") (pin "3") (pinfunction "D_3") (pintype "passive"))
    )
    (net (code "26") (name "Net-(D5-A)") (class "Default")
      (node (ref "C_1uf_6") (pin "2") (pinfunction "2_2") (pintype "passive"))
      (node (ref "D5") (pin "2") (pinfunction "A_2") (pintype "passive"))
      (node (ref "JM4") (pin "2") (pinfunction "2_2") (pintype "passive"))
      (node (ref "Q4") (pin "3") (pinfunction "D_3") (pintype "passive"))
    )
    (net (code "27") (name "Net-(IMU-AD0)") (class "Default")
      (node (ref "IMU") (pin "9") (pinfunction "AD0_9") (pintype "passive"))
      (node (ref "R_4.7k") (pin "2") (pinfunction "2_2") (pintype "passive"))
    )
    (net (code "28") (name "Net-(IMU-CPOUT)") (class "Default")
      (node (ref "C_0.1uf_4") (pin "1") (pinfunction "1_1") (pintype "passive"))
      (node (ref "IMU") (pin "20") (pinfunction "CPOUT_20") (pintype "passive"))
    )
    (net (code "29") (name "Net-(IMU-REGOUT)") (class "Default")
      (node (ref "C_0.1uf_3") (pin "2") (pinfunction "2_2") (pintype "passive"))
      (node (ref "IMU") (pin "10") (pinfunction "REGOUT_10") (pintype "passive"))
    )
    (net (code "30") (name "Net-(LED_b-K)") (class "Default")
      (node (ref "LED_b") (pin "1") (pinfunction "K_1") (pintype "passive"))
      (node (ref "RL_1K_3") (pin "2") (pinfunction "2_2") (pintype "passive"))
    )
    (net (code "31") (name "Net-(LED_g-K)") (class "Default")
      (node (ref "LED_g") (pin "1") (pinfunction "K_1") (pintype "passive"))
      (node (ref "RL_1K_1") (pin "2") (pinfunction "2_2") (pintype "passive"))
    )
    (net (code "32") (name "Net-(LED_r-K)") (class "Default")
      (node (ref "LED_r") (pin "1") (pinfunction "K_1") (pintype "passive"))
      (node (ref "RL_1K_2") (pin "2") (pinfunction "2_2") (pintype "passive"))
    )
    (net (code "33") (name "Net-(Select-COM_1)") (class "Default")
      (node (ref "R6_3.3k") (pin "1") (pinfunction "1_1") (pintype "passive"))
      (node (ref "Select") (pin "1") (pinfunction "COM_1_1") (pintype "passive"))
    )
    (net (code "34") (name "Net-(Select-COM_2)") (class "Default")
      (node (ref "R7_2.4k") (pin "2") (pinfunction "2_2") (pintype "passive"))
      (node (ref "Select") (pin "2") (pinfunction "COM_2_2") (pintype "passive"))
    )
    (net (code "35") (name "Net-(Select-COM_3)") (class "Default")
      (node (ref "R8_1.2k") (pin "2") (pinfunction "2_2") (pintype "passive"))
      (node (ref "Select") (pin "3") (pinfunction "COM_3_3") (pintype "passive"))
    )
    (net (code "36") (name "Net-(Select-NO_1)") (class "Default")
      (node (ref "Select") (pin "4") (pinfunction "NO_1_4") (pintype "passive"))
      (node (ref "Select") (pin "5") (pinfunction "NO_2_5") (pintype "passive"))
      (node (ref "Select") (pin "6") (pinfunction "NO_3_6") (pintype "passive"))
      (node (ref "battery_charger") (pin "2") (pinfunction "PROG2_2") (pintype "passive"))
    )
    (net (code "37") (name "Net-(USB_C_conn-CC1)") (class "Default")
      (node (ref "R2_5.1k") (pin "2") (pinfunction "2_2") (pintype "passive"))
      (node (ref "USB_C_conn") (pin "A5") (pinfunction "CC1_A5") (pintype "bidirectional"))
    )
    (net (code "38") (name "Net-(USB_C_conn-CC2)") (class "Default")
      (node (ref "R1_5.1k") (pin "2") (pinfunction "2_2") (pintype "passive"))
      (node (ref "USB_C_conn") (pin "B5") (pinfunction "CC2_B5") (pintype "bidirectional"))
    )
    (net (code "39") (name "Net-(USB_to_UART-RXD)") (class "Default")
      (node (ref "R11_1k") (pin "1") (pinfunction "1_1") (pintype "passive"))
      (node (ref "R12_1k") (pin "1") (pinfunction "1_1") (pintype "passive"))
      (node (ref "USB_to_UART") (pin "25") (pinfunction "RXD_25") (pintype "passive"))
      (node (ref "USB_to_UART") (pin "26") (pinfunction "TXD_26") (pintype "passive"))
    )
    (net (code "40") (name "Net-(USB_to_UART-VBUS)") (class "Default")
      (node (ref "R13_47.5k") (pin "2") (pinfunction "2_2") (pintype "passive"))
      (node (ref "R14_22.1k") (pin "2") (pinfunction "2_2") (pintype "passive"))
      (node (ref "USB_to_UART") (pin "8") (pinfunction "VBUS_8") (pintype "passive"))
    )
    (net (code "41") (name "Net-(USB_to_UART-~{RST})") (class "Default")
      (node (ref "R15_10k") (pin "2") (pinfunction "2_2") (pintype "passive"))
      (node (ref "USB_to_UART") (pin "9") (pinfunction "~{RST}_9") (pintype "passive"))
    )
    (net (code "42") (name "Net-(battery_charger-~{CHRG})") (class "Default")
      (node (ref "R4_1k") (pin "1") (pinfunction "1_1") (pintype "passive"))
      (node (ref "battery_charger") (pin "7") (pinfunction "~{CHRG}_7") (pintype "passive"))
    )
    (net (code "43") (name "Net-(battery_charger-~{STDBY})") (class "Default")
      (node (ref "R5_1k") (pin "1") (pinfunction "1_1") (pintype "passive"))
      (node (ref "battery_charger") (pin "6") (pinfunction "~{STDBY}_6") (pintype "passive"))
    )
    (net (code "44") (name "Net-(charging_led-K)") (class "Default")
      (node (ref "R4_1k") (pin "2") (pinfunction "2_2") (pintype "passive"))
      (node (ref "charging_led") (pin "1") (pinfunction "K_1") (pintype "passive"))
    )
    (net (code "45") (name "Net-(on/off_led-A)") (class "Default")
      (node (ref "R3_470") (pin "2") (pinfunction "2_2") (pintype "passive"))
      (node (ref "on/off_led") (pin "2") (pinfunction "A_2") (pintype "passive"))
    )
    (net (code "46") (name "Net-(on/off_led_batt-K)") (class "Default")
      (node (ref "R5_1k") (pin "2") (pinfunction "2_2") (pintype "passive"))
      (node (ref "on/off_led_batt") (pin "1") (pinfunction "K_1") (pintype "passive"))
    )
    (net (code "47") (name "RTS") (class "Default")
      (node (ref "DPOT") (pin "1") (pinfunction "E1_1") (pintype "passive"))
      (node (ref "DPOT") (pin "5") (pinfunction "B2_5") (pintype "passive"))
      (node (ref "USB_to_UART") (pin "24") (pinfunction "RTS_24") (pintype "passive"))
    )
    (net (code "48") (name "RX") (class "Default")
      (node (ref "ESP32") (pin "34") (pinfunction "RXD0_34") (pintype "passive"))
      (node (ref "R12_1k") (pin "2") (pinfunction "2_2") (pintype "passive"))
    )
    (net (code "49") (name "RXD2") (class "Default")
      (node (ref "ESP32") (pin "27") (pinfunction "IO16_27") (pintype "passive"))
      (node (ref "I2C connector") (pin "3") (pinfunction "3_3") (pintype "passive"))
    )
    (net (code "50") (name "SCL") (class "Default")
      (node (ref "ESP32") (pin "36") (pinfunction "IO22_36") (pintype "passive"))
      (node (ref "I2C connector") (pin "6") (pinfunction "6_6") (pintype "passive"))
      (node (ref "IMU") (pin "23") (pinfunction "SCL_23") (pintype "passive"))
      (node (ref "R18_10k") (pin "2") (pinfunction "2_2") (pintype "passive"))
    )
    (net (code "51") (name "SDA") (class "Default")
      (node (ref "ESP32") (pin "33") (pinfunction "IO21_33") (pintype "passive"))
      (node (ref "I2C connector") (pin "5") (pinfunction "5_5") (pintype "passive"))
      (node (ref "IMU") (pin "24") (pinfunction "SDA_24") (pintype "passive"))
      (node (ref "R17_10k") (pin "2") (pinfunction "2_2") (pintype "passive"))
    )
    (net (code "52") (name "SRV_1") (class "Default")
      (node (ref "ESP32") (pin "14") (pinfunction "IO12_14") (pintype "passive"))
      (node (ref "PWM_signals") (pin "3") (pinfunction "3_3") (pintype "passive"))
    )
    (net (code "53") (name "SRV_2") (class "Default")
      (node (ref "ESP32") (pin "13") (pinfunction "IO14_13") (pintype "passive"))
      (node (ref "PWM_signals") (pin "4") (pinfunction "4_4") (pintype "passive"))
    )
    (net (code "54") (name "SRV_3") (class "Default")
      (node (ref "ESP32") (pin "12") (pinfunction "IO27_12") (pintype "passive"))
      (node (ref "PWM_signals") (pin "5") (pinfunction "5_5") (pintype "passive"))
    )
    (net (code "55") (name "SRV_4") (class "Default")
      (node (ref "ESP32") (pin "11") (pinfunction "IO26_11") (pintype "passive"))
      (node (ref "PWM_signals") (pin "6") (pinfunction "6_6") (pintype "passive"))
    )
    (net (code "56") (name "Sw_in") (class "Default")
      (node (ref "5-3.3v LDO") (pin "3") (pinfunction "EN_3") (pintype "passive"))
      (node (ref "ON/OFF_Sw") (pin "2") (pinfunction "COM_2") (pintype "passive"))
    )
    (net (code "57") (name "TX") (class "Default")
      (node (ref "ESP32") (pin "35") (pinfunction "TXD0_35") (pintype "passive"))
      (node (ref "R11_1k") (pin "2") (pinfunction "2_2") (pintype "passive"))
    )
    (net (code "58") (name "TXD2") (class "Default")
      (node (ref "ESP32") (pin "28") (pinfunction "IO17_28") (pintype "passive"))
      (node (ref "I2C connector") (pin "4") (pinfunction "4_4") (pintype "passive"))
    )
    (net (code "59") (name "VBUS") (class "Default")
      (node (ref "C_0.1uf") (pin "2") (pinfunction "2_2") (pintype "passive"))
      (node (ref "C_10uf") (pin "2") (pinfunction "2_2") (pintype "passive"))
      (node (ref "D1") (pin "A") (pinfunction "A_A") (pintype "passive"))
      (node (ref "ON/OFF_Sw") (pin "1") (pinfunction "NC_1") (pintype "passive"))
      (node (ref "PMOS") (pin "1") (pinfunction "G_1") (pintype "passive"))
      (node (ref "R14_22.1k") (pin "1") (pinfunction "1_1") (pintype "passive"))
      (node (ref "USB_C_conn") (pin "A4") (pinfunction "VBUS_A4") (pintype "power_in"))
      (node (ref "USB_C_conn") (pin "A9") (pinfunction "VBUS_A9") (pintype "power_in"))
      (node (ref "USB_C_conn") (pin "B4") (pinfunction "VBUS_B4") (pintype "power_in"))
      (node (ref "USB_C_conn") (pin "B9") (pinfunction "VBUS_B9") (pintype "power_in"))
      (node (ref "USB_to_UART") (pin "7") (pinfunction "REGIN_7") (pintype "passive"))
      (node (ref "battery_charger") (pin "4") (pinfunction "VCC4_4") (pintype "passive"))
      (node (ref "battery_charger") (pin "8") (pinfunction "CE_8") (pintype "passive"))
      (node (ref "charging_led") (pin "2") (pinfunction "A_2") (pintype "passive"))
      (node (ref "on/off_led_batt") (pin "2") (pinfunction "A_2") (pintype "passive"))
    )
    (net (code "60") (name "VDD") (class "Default")
      (node (ref "C_1uf") (pin "2") (pinfunction "2_2") (pintype "passive"))
      (node (ref "R15_10k") (pin "1") (pinfunction "1_1") (pintype "passive"))
      (node (ref "USB_to_UART") (pin "6") (pinfunction "VDD_6") (pintype "passive"))
    )
    (net (code "61") (name "byp") (class "Default")
      (node (ref "5-3.3v LDO") (pin "4") (pinfunction "BYP_4") (pintype "passive"))
      (node (ref "C4_10uf") (pin "1") (pinfunction "1_1") (pintype "passive"))
    )
    (net (code "62") (name "unconnected-(ESP32-3V3-Pad2)") (class "Default")
      (node (ref "ESP32") (pin "2") (pinfunction "3V3_2") (pintype "passive"))
    )
    (net (code "63") (name "unconnected-(ESP32-NC_1-Pad17)") (class "Default")
      (node (ref "ESP32") (pin "17") (pinfunction "NC_1_17") (pintype "passive+no_connect"))
    )
    (net (code "64") (name "unconnected-(ESP32-NC_2-Pad18)") (class "Default")
      (node (ref "ESP32") (pin "18") (pinfunction "NC_2_18") (pintype "passive+no_connect"))
    )
    (net (code "65") (name "unconnected-(ESP32-NC_3-Pad19)") (class "Default")
      (node (ref "ESP32") (pin "19") (pinfunction "NC_3_19") (pintype "passive+no_connect"))
    )
    (net (code "66") (name "unconnected-(ESP32-NC_4-Pad20)") (class "Default")
      (node (ref "ESP32") (pin "20") (pinfunction "NC_4_20") (pintype "passive+no_connect"))
    )
    (net (code "67") (name "unconnected-(ESP32-NC_5-Pad21)") (class "Default")
      (node (ref "ESP32") (pin "21") (pinfunction "NC_5_21") (pintype "passive+no_connect"))
    )
    (net (code "68") (name "unconnected-(ESP32-NC_6-Pad22)") (class "Default")
      (node (ref "ESP32") (pin "22") (pinfunction "NC_6_22") (pintype "passive+no_connect"))
    )
    (net (code "69") (name "unconnected-(ESP32-NC_7-Pad32)") (class "Default")
      (node (ref "ESP32") (pin "32") (pinfunction "NC_7_32") (pintype "passive+no_connect"))
    )
    (net (code "70") (name "unconnected-(ESP32-SENSOR_VN-Pad5)") (class "Default")
      (node (ref "ESP32") (pin "5") (pinfunction "SENSOR_VN_5") (pintype "passive+no_connect"))
    )
    (net (code "71") (name "unconnected-(ESP32-SENSOR_VP-Pad4)") (class "Default")
      (node (ref "ESP32") (pin "4") (pinfunction "SENSOR_VP_4") (pintype "passive+no_connect"))
    )
    (net (code "72") (name "unconnected-(IMU-AUX_CL-Pad7)") (class "Default")
      (node (ref "IMU") (pin "7") (pinfunction "AUX_CL_7") (pintype "passive+no_connect"))
    )
    (net (code "73") (name "unconnected-(IMU-AUX_DA-Pad6)") (class "Default")
      (node (ref "IMU") (pin "6") (pinfunction "AUX_DA_6") (pintype "passive+no_connect"))
    )
    (net (code "74") (name "unconnected-(IMU-EP-Pad25)") (class "Default")
      (node (ref "IMU") (pin "25") (pinfunction "EP_25") (pintype "passive+no_connect"))
    )
    (net (code "75") (name "unconnected-(IMU-INT-Pad12)") (class "Default")
      (node (ref "IMU") (pin "12") (pinfunction "INT_12") (pintype "passive"))
    )
    (net (code "76") (name "unconnected-(IMU-NC_1-Pad2)") (class "Default")
      (node (ref "IMU") (pin "2") (pinfunction "NC_1_2") (pintype "passive+no_connect"))
    )
    (net (code "77") (name "unconnected-(IMU-NC_2-Pad3)") (class "Default")
      (node (ref "IMU") (pin "3") (pinfunction "NC_2_3") (pintype "passive+no_connect"))
    )
    (net (code "78") (name "unconnected-(IMU-NC_3-Pad4)") (class "Default")
      (node (ref "IMU") (pin "4") (pinfunction "NC_3_4") (pintype "passive+no_connect"))
    )
    (net (code "79") (name "unconnected-(IMU-NC_4-Pad5)") (class "Default")
      (node (ref "IMU") (pin "5") (pinfunction "NC_4_5") (pintype "passive+no_connect"))
    )
    (net (code "80") (name "unconnected-(IMU-NC_5-Pad14)") (class "Default")
      (node (ref "IMU") (pin "14") (pinfunction "NC_5_14") (pintype "passive+no_connect"))
    )
    (net (code "81") (name "unconnected-(IMU-NC_6-Pad15)") (class "Default")
      (node (ref "IMU") (pin "15") (pinfunction "NC_6_15") (pintype "passive+no_connect"))
    )
    (net (code "82") (name "unconnected-(IMU-NC_7-Pad16)") (class "Default")
      (node (ref "IMU") (pin "16") (pinfunction "NC_7_16") (pintype "passive+no_connect"))
    )
    (net (code "83") (name "unconnected-(IMU-NC_8-Pad17)") (class "Default")
      (node (ref "IMU") (pin "17") (pinfunction "NC_8_17") (pintype "passive+no_connect"))
    )
    (net (code "84") (name "unconnected-(IMU-RESV_1-Pad19)") (class "Default")
      (node (ref "IMU") (pin "19") (pinfunction "RESV_1_19") (pintype "passive+no_connect"))
    )
    (net (code "85") (name "unconnected-(IMU-RESV_2-Pad21)") (class "Default")
      (node (ref "IMU") (pin "21") (pinfunction "RESV_2_21") (pintype "passive+no_connect"))
    )
    (net (code "86") (name "unconnected-(IMU-RESV_3-Pad22)") (class "Default")
      (node (ref "IMU") (pin "22") (pinfunction "RESV_3_22") (pintype "passive+no_connect"))
    )
    (net (code "87") (name "unconnected-(USB_C_conn-SBU1-PadA8)") (class "Default")
      (node (ref "USB_C_conn") (pin "A8") (pinfunction "SBU1_A8") (pintype "bidirectional+no_connect"))
    )
    (net (code "88") (name "unconnected-(USB_C_conn-SBU2-PadB8)") (class "Default")
      (node (ref "USB_C_conn") (pin "B8") (pinfunction "SBU2_B8") (pintype "bidirectional+no_connect"))
    )
    (net (code "89") (name "unconnected-(USB_to_UART-CTS-Pad23)") (class "Default")
      (node (ref "USB_to_UART") (pin "23") (pinfunction "CTS_23") (pintype "passive+no_connect"))
    )
    (net (code "90") (name "unconnected-(USB_to_UART-DCD-Pad1)") (class "Default")
      (node (ref "USB_to_UART") (pin "1") (pinfunction "DCD_1") (pintype "passive+no_connect"))
    )
    (net (code "91") (name "unconnected-(USB_to_UART-DSR-Pad27)") (class "Default")
      (node (ref "USB_to_UART") (pin "27") (pinfunction "DSR_27") (pintype "passive+no_connect"))
    )
    (net (code "92") (name "unconnected-(USB_to_UART-NC_1-Pad10)") (class "Default")
      (node (ref "USB_to_UART") (pin "10") (pinfunction "NC_1_10") (pintype "passive+no_connect"))
    )
    (net (code "93") (name "unconnected-(USB_to_UART-NC_2-Pad13)") (class "Default")
      (node (ref "USB_to_UART") (pin "13") (pinfunction "NC_2_13") (pintype "passive+no_connect"))
    )
    (net (code "94") (name "unconnected-(USB_to_UART-NC_3-Pad14)") (class "Default")
      (node (ref "USB_to_UART") (pin "14") (pinfunction "NC_3_14") (pintype "passive+no_connect"))
    )
    (net (code "95") (name "unconnected-(USB_to_UART-NC_4-Pad15)") (class "Default")
      (node (ref "USB_to_UART") (pin "15") (pinfunction "NC_4_15") (pintype "passive+no_connect"))
    )
    (net (code "96") (name "unconnected-(USB_to_UART-NC_5-Pad16)") (class "Default")
      (node (ref "USB_to_UART") (pin "16") (pinfunction "NC_5_16") (pintype "passive+no_connect"))
    )
    (net (code "97") (name "unconnected-(USB_to_UART-NC_6-Pad17)") (class "Default")
      (node (ref "USB_to_UART") (pin "17") (pinfunction "NC_6_17") (pintype "passive+no_connect"))
    )
    (net (code "98") (name "unconnected-(USB_to_UART-NC_7-Pad19)") (class "Default")
      (node (ref "USB_to_UART") (pin "19") (pinfunction "NC_7_19") (pintype "passive+no_connect"))
    )
    (net (code "99") (name "unconnected-(USB_to_UART-NC_8-Pad20)") (class "Default")
      (node (ref "USB_to_UART") (pin "20") (pinfunction "NC_8_20") (pintype "passive+no_connect"))
    )
    (net (code "100") (name "unconnected-(USB_to_UART-NC_9-Pad21)") (class "Default")
      (node (ref "USB_to_UART") (pin "21") (pinfunction "NC_9_21") (pintype "passive+no_connect"))
    )
    (net (code "101") (name "unconnected-(USB_to_UART-NC_10-Pad22)") (class "Default")
      (node (ref "USB_to_UART") (pin "22") (pinfunction "NC_10_22") (pintype "passive+no_connect"))
    )
    (net (code "102") (name "unconnected-(USB_to_UART-NC{slash}VPP-Pad18)") (class "Default")
      (node (ref "USB_to_UART") (pin "18") (pinfunction "NC/VPP_18") (pintype "passive+no_connect"))
    )
    (net (code "103") (name "unconnected-(USB_to_UART-RI-Pad2)") (class "Default")
      (node (ref "USB_to_UART") (pin "2") (pinfunction "RI_2") (pintype "passive+no_connect"))
    )
    (net (code "104") (name "unconnected-(USB_to_UART-SUSPEND-Pad12)") (class "Default")
      (node (ref "USB_to_UART") (pin "12") (pinfunction "SUSPEND_12") (pintype "passive+no_connect"))
    )
    (net (code "105") (name "unconnected-(USB_to_UART-~{SUSPEND}-Pad11)") (class "Default")
      (node (ref "USB_to_UART") (pin "11") (pinfunction "~{SUSPEND}_11") (pintype "passive+no_connect"))
    )
  )
)
